# USB-Adapter.net
KiCad netlist of a schematic drawn in EAGLE
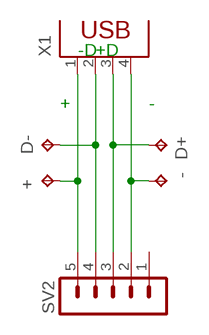
[diagram p0: schematic, sheet 1]

(export (version "E")
  (design (tool "Eeschema 10.0.6"))
  (components
    (comp (ref "+")
      (value "TPPAD1-13")
      (footprint "eagle-import:P1-13")
      (libsource (lib "eagle-import") (part "TPPAD1-13"))
    )
    (comp (ref "-")
      (value "TPPAD1-13")
      (footprint "eagle-import:P1-13")
      (libsource (lib "eagle-import") (part "TPPAD1-13"))
    )
    (comp (ref "D+")
      (value "TPPAD1-13")
      (footprint "eagle-import:P1-13")
      (libsource (lib "eagle-import") (part "TPPAD1-13"))
    )
    (comp (ref "D-")
      (value "TPPAD1-13")
      (footprint "eagle-import:P1-13")
      (libsource (lib "eagle-import") (part "TPPAD1-13"))
    )
    (comp (ref "SV2")
      (value "MA05-1")
      (footprint "eagle-import:MA05-1")
      (libsource (lib "eagle-import") (part "MA05-1"))
    )
    (comp (ref "X1")
      (value "PN87520")
      (footprint "eagle-import:PN87520")
      (libsource (lib "eagle-import") (part "PN87520"))
    )
  )
  (nets
    (net (code "1") (name "Net-(+-PadTP)") (class "Default")
      (node (ref "+") (pin "TP") (pinfunction "TP_TP") (pintype "input"))
      (node (ref "SV2") (pin "5") (pinfunction "5_5") (pintype "passive"))
      (node (ref "X1") (pin "1") (pinfunction "1_1") (pintype "passive"))
    )
    (net (code "2") (name "Net-(--PadTP)") (class "Default")
      (node (ref "-") (pin "TP") (pinfunction "TP_TP") (pintype "input"))
      (node (ref "SV2") (pin "2") (pinfunction "2_2") (pintype "passive"))
      (node (ref "X1") (pin "4") (pinfunction "4_4") (pintype "passive"))
    )
    (net (code "3") (name "Net-(D+-PadTP)") (class "Default")
      (node (ref "D+") (pin "TP") (pinfunction "TP_TP") (pintype "input"))
      (node (ref "SV2") (pin "3") (pinfunction "3_3") (pintype "passive"))
      (node (ref "X1") (pin "3") (pinfunction "3_3") (pintype "passive"))
    )
    (net (code "4") (name "Net-(D--PadTP)") (class "Default")
      (node (ref "D-") (pin "TP") (pinfunction "TP_TP") (pintype "input"))
      (node (ref "SV2") (pin "4") (pinfunction "4_4") (pintype "passive"))
      (node (ref "X1") (pin "2") (pinfunction "2_2") (pintype "passive"))
    )
    (net (code "5") (name "unconnected-(SV2-Pad1)") (class "Default")
      (node (ref "SV2") (pin "1") (pinfunction "1_1") (pintype "passive"))
    )
  )
)
